# TrafficLights.net
KiCad netlist of a schematic drawn in EAGLE
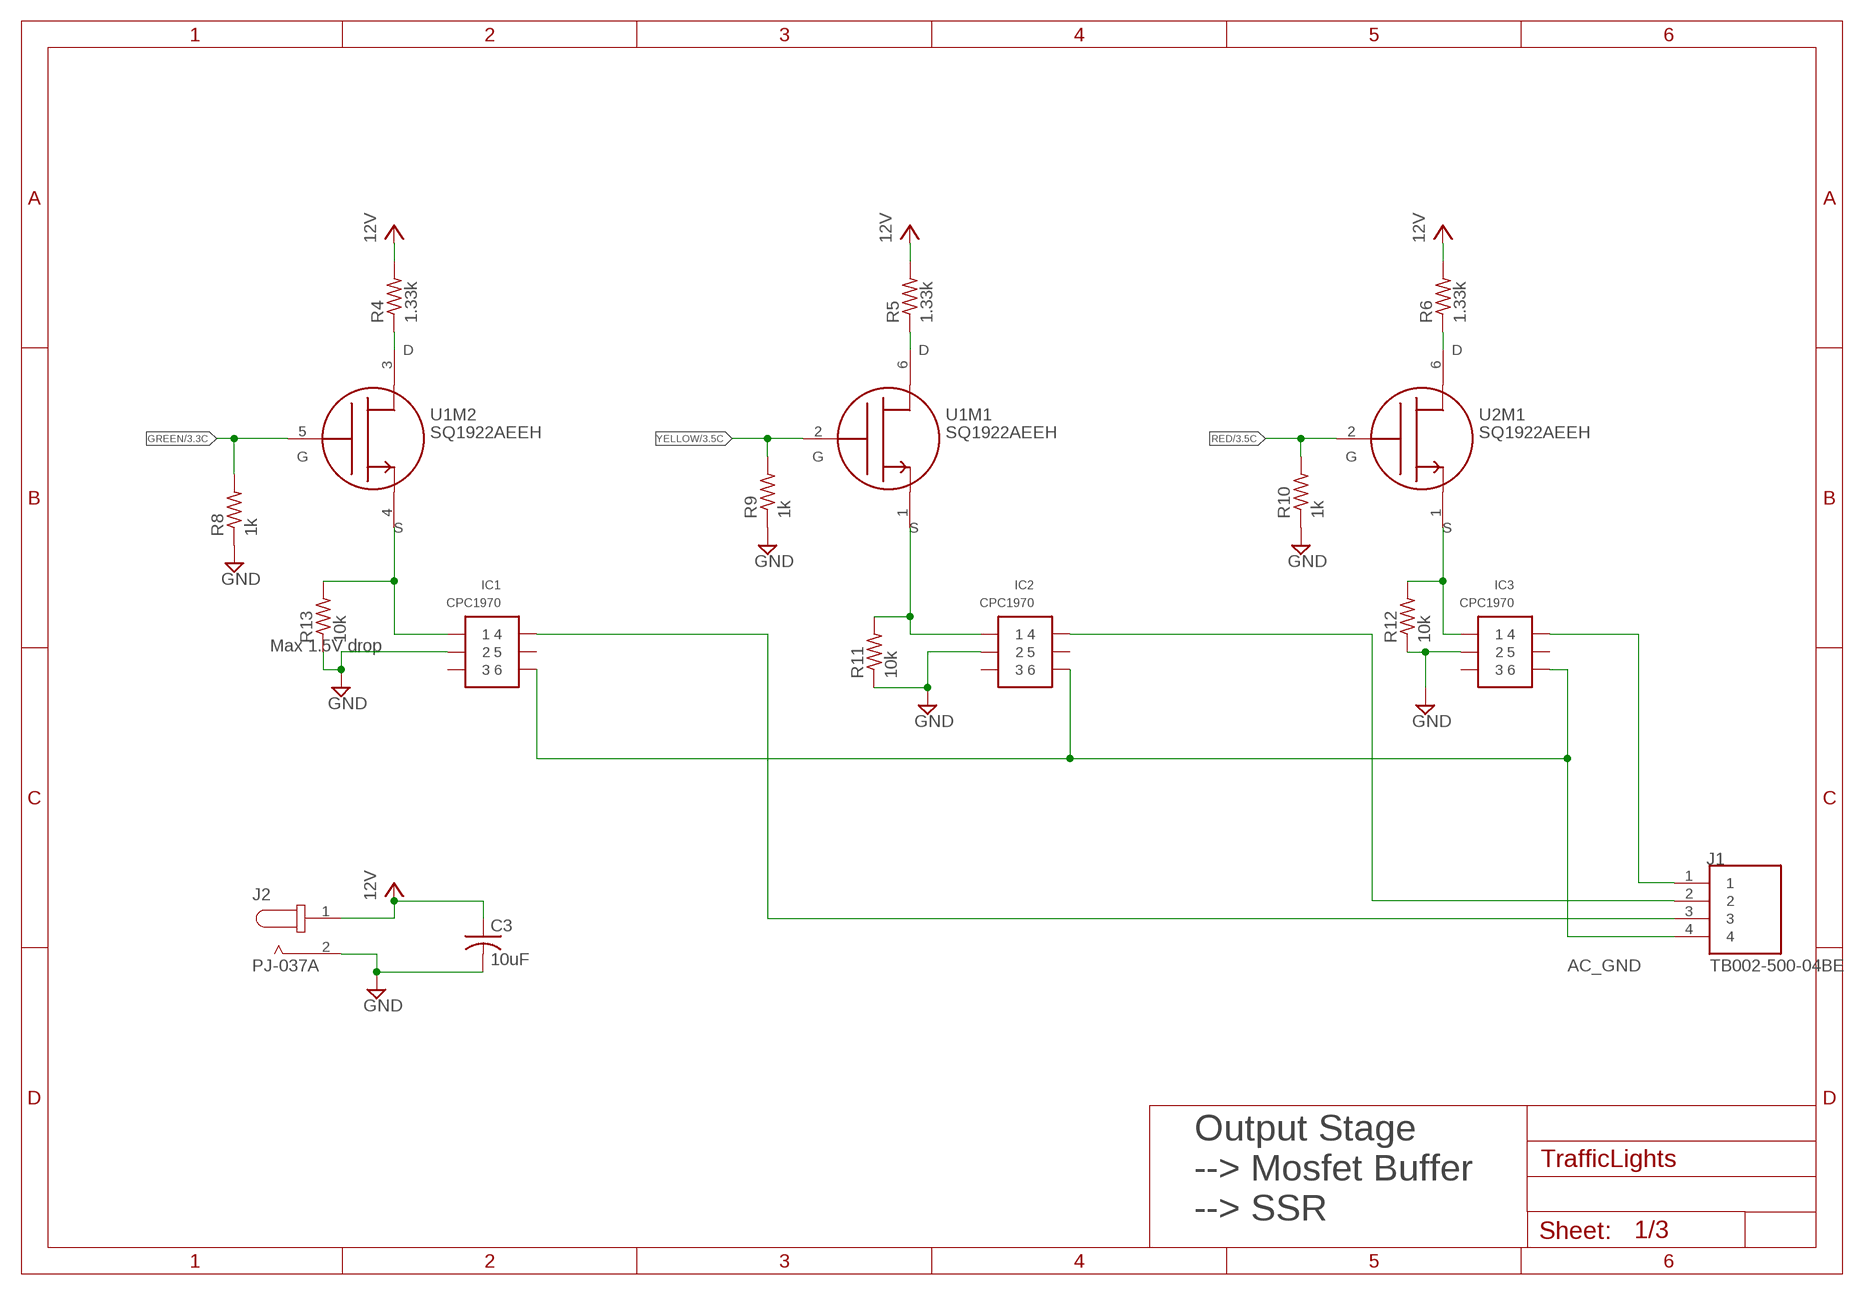
[diagram p0: schematic, sheet 1]
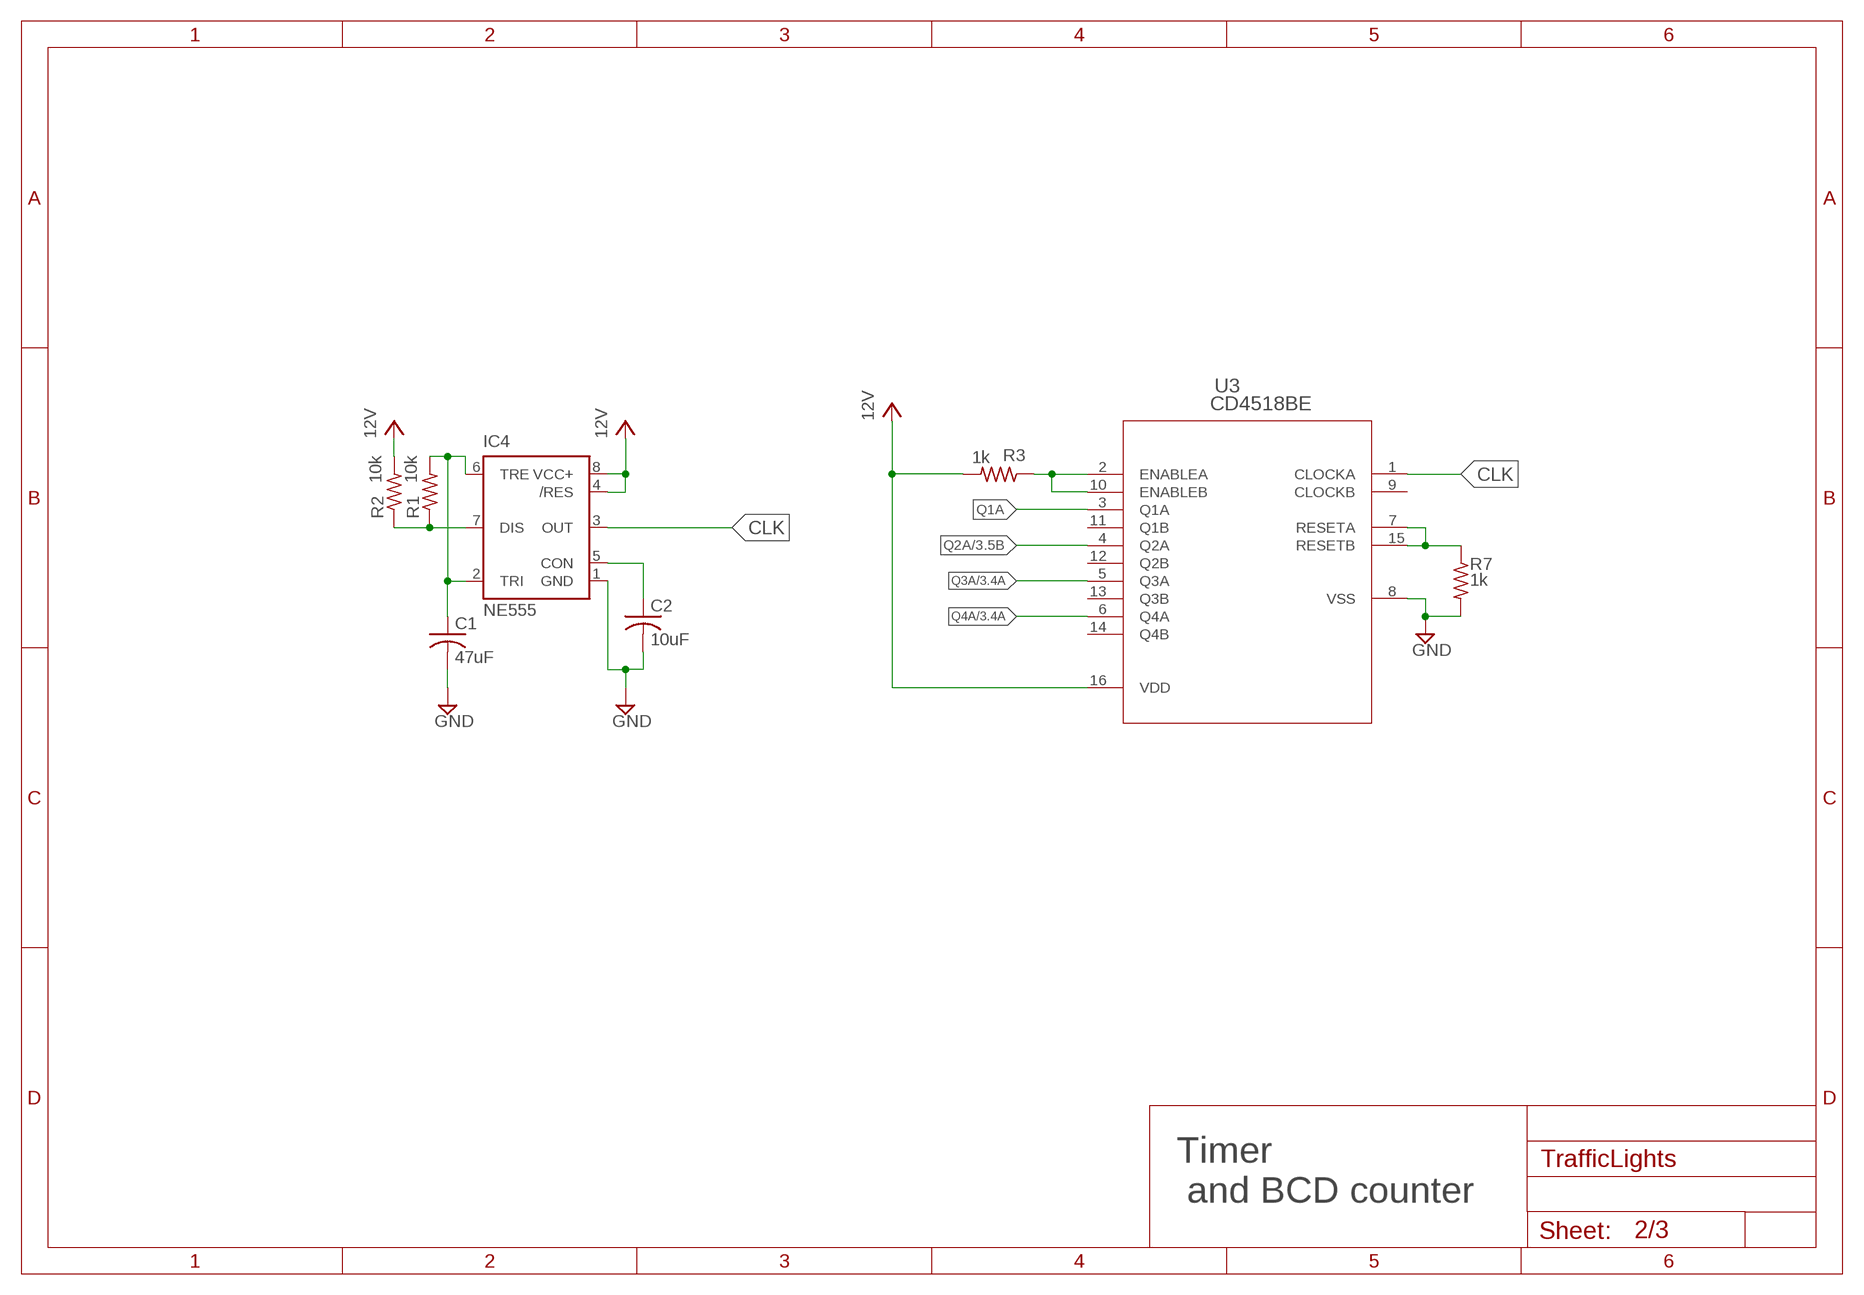
[diagram p1: schematic, sheet 2]
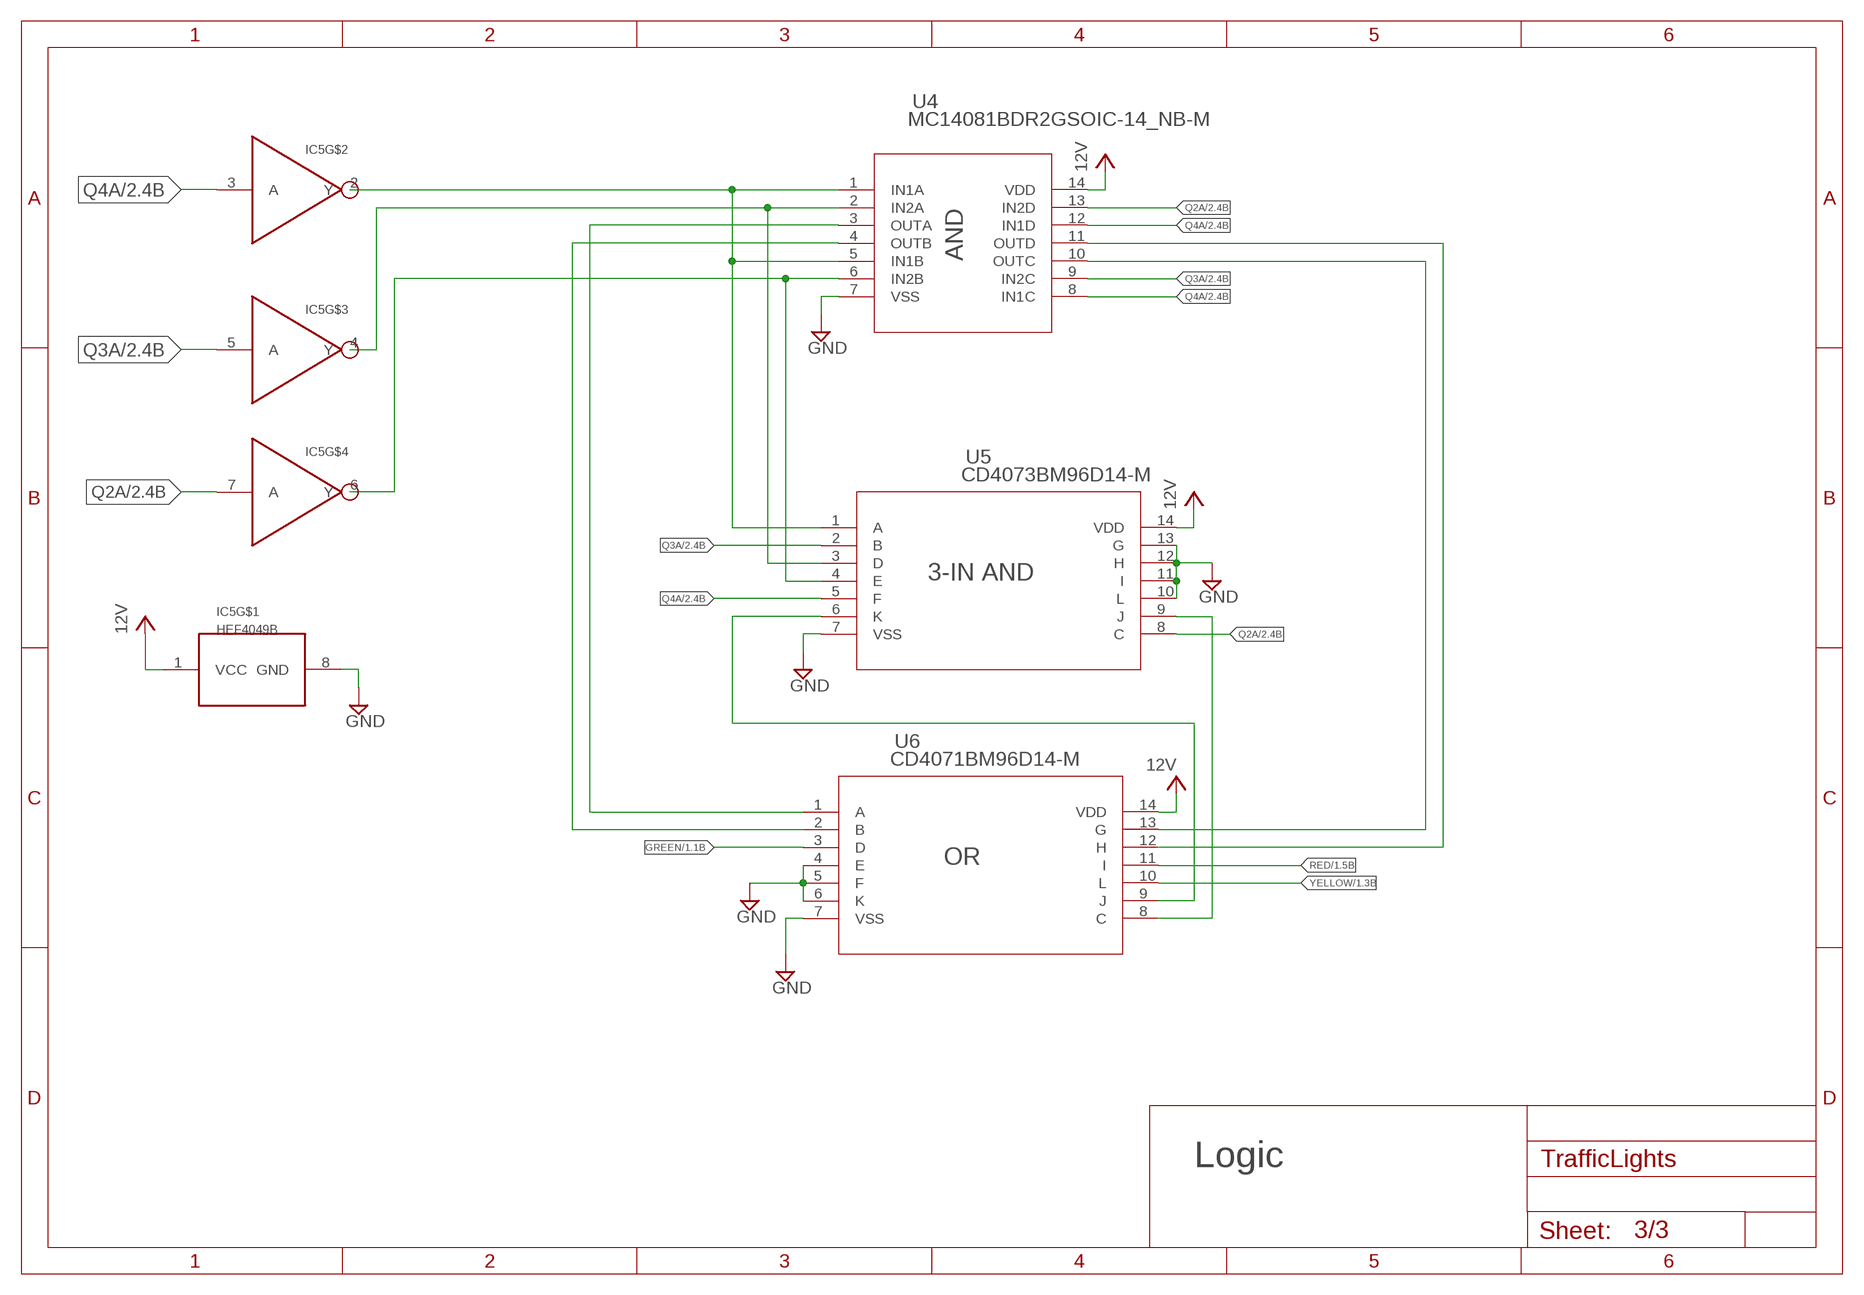
[diagram p2: schematic, sheet 3]

(export (version "E")
  (design (tool "Eeschema 10.0.6"))
  (components
    (comp (ref "IC5")
      (value "HEF4049B")
      (footprint "eagle-import:SO16")
      (libsource (lib "eagle-import") (part "HEF4049B"))
    )
    (comp (ref "U4")
      (value "MC14081BDR2GSOIC-14_NB-M")
      (footprint "eagle-import:SOIC-14_NB-M")
      (fields (field (name "MANUFACTURER_PART_NUMBER") "MC14081BDR2G"))
      (libsource (lib "eagle-import") (part "MC14081BDR2GSOIC-14_NB-M"))
    )
    (comp (ref "U5")
      (value "CD4073BM96D14-M")
      (footprint "eagle-import:D14-M")
      (fields (field (name "MANUFACTURER_PART_NUMBER") "CD4073BM96"))
      (libsource (lib "eagle-import") (part "CD4073BM96D14-M"))
    )
    (comp (ref "U6")
      (value "CD4071BM96D14-M")
      (footprint "eagle-import:D14-M")
      (fields (field (name "MANUFACTURER_PART_NUMBER") "CD4073BM96"))
      (libsource (lib "eagle-import") (part "CD4073BM96D14-M"))
    )
    (comp (ref "C1")
      (value "47uF")
      (footprint "eagle-import:C1206")
      (libsource (lib "eagle-import") (part "C-USC1206"))
    )
    (comp (ref "C2")
      (value "10uF")
      (footprint "eagle-import:C1206")
      (libsource (lib "eagle-import") (part "C-USC1206"))
    )
    (comp (ref "IC4")
      (value "NE555")
      (footprint "eagle-import:DIL-08")
      (fields (field (name "MF") "Arrow Electronics") (field (name "MPN") "NE555N"))
      (libsource (lib "eagle-import") (part "NE555"))
    )
    (comp (ref "R1")
      (value "10k")
      (footprint "eagle-import:R1206")
      (libsource (lib "eagle-import") (part "R-US_R1206"))
    )
    (comp (ref "R2")
      (value "10k")
      (footprint "eagle-import:R1206")
      (libsource (lib "eagle-import") (part "R-US_R1206"))
    )
    (comp (ref "R3")
      (value "1k")
      (footprint "eagle-import:R1206")
      (libsource (lib "eagle-import") (part "R-US_R1206"))
    )
    (comp (ref "R7")
      (value "1k")
      (footprint "eagle-import:R1206")
      (libsource (lib "eagle-import") (part "R-US_R1206"))
    )
    (comp (ref "U3")
      (value "CD4518BE")
      (footprint "eagle-import:N16")
      (libsource (lib "eagle-import") (part "CD4518BE"))
    )
    (comp (ref "C3")
      (value "10uF")
      (footprint "eagle-import:C1206")
      (libsource (lib "eagle-import") (part "C-USC1206"))
    )
    (comp (ref "IC1")
      (value "CPC1970")
      (footprint "eagle-import:6-DIP")
      (fields (field (name "MANUFACTURER_PART_NUMBER") "CPC1972G"))
      (libsource (lib "eagle-import") (part "CPC1972"))
    )
    (comp (ref "IC2")
      (value "CPC1970")
      (footprint "eagle-import:6-DIP")
      (fields (field (name "MANUFACTURER_PART_NUMBER") "CPC1972G"))
      (libsource (lib "eagle-import") (part "CPC1972"))
    )
    (comp (ref "IC3")
      (value "CPC1970")
      (footprint "eagle-import:6-DIP")
      (fields (field (name "MANUFACTURER_PART_NUMBER") "CPC1972G"))
      (libsource (lib "eagle-import") (part "CPC1972"))
    )
    (comp (ref "J1")
      (value "TB002-500-04BE")
      (footprint "eagle-import:CUI_TB002-500-04BE")
      (fields (field (name "MANUFACTURER") "CUI"))
      (libsource (lib "eagle-import") (part "TB002-500-04BE"))
    )
    (comp (ref "J2")
      (value "PJ-037A")
      (footprint "eagle-import:CUI_PJ-037A")
      (fields (field (name "DIGI-KEY_PART_NUMBER") "CP-037A-ND") (field (name "MF") "CUI Inc."))
      (libsource (lib "eagle-import") (part "PJ-037A"))
    )
    (comp (ref "R4")
      (value "1.33k")
      (footprint "eagle-import:R1206")
      (libsource (lib "eagle-import") (part "R-US_R1206"))
    )
    (comp (ref "R5")
      (value "1.33k")
      (footprint "eagle-import:R1206")
      (libsource (lib "eagle-import") (part "R-US_R1206"))
    )
    (comp (ref "R6")
      (value "1.33k")
      (footprint "eagle-import:R1206")
      (libsource (lib "eagle-import") (part "R-US_R1206"))
    )
    (comp (ref "R8")
      (value "1k")
      (footprint "eagle-import:R1206")
      (libsource (lib "eagle-import") (part "R-US_R1206"))
    )
    (comp (ref "R9")
      (value "1k")
      (footprint "eagle-import:R1206")
      (libsource (lib "eagle-import") (part "R-US_R1206"))
    )
    (comp (ref "R10")
      (value "1k")
      (footprint "eagle-import:R1206")
      (libsource (lib "eagle-import") (part "R-US_R1206"))
    )
    (comp (ref "R11")
      (value "10k")
      (footprint "eagle-import:0207_2V")
      (libsource (lib "eagle-import") (part "R-US_0207/2V"))
    )
    (comp (ref "R12")
      (value "10k")
      (footprint "eagle-import:0207_2V")
      (libsource (lib "eagle-import") (part "R-US_0207/2V"))
    )
    (comp (ref "R13")
      (value "10k")
      (footprint "eagle-import:R1206")
      (libsource (lib "eagle-import") (part "R-US_R1206"))
    )
    (comp (ref "U1")
      (value "SQ1922AEEH")
      (footprint "eagle-import:SOT-363")
      (fields (field (name "MANUFACTURER_PART_NUMBER") "SQ1922AEEH-T1_GE3"))
      (libsource (lib "eagle-import") (part "SQ1922AEEH"))
    )
    (comp (ref "U2")
      (value "SQ1922AEEH")
      (footprint "eagle-import:SOT-363")
      (fields (field (name "MANUFACTURER_PART_NUMBER") "SQ1922AEEH-T1_GE3"))
      (libsource (lib "eagle-import") (part "SQ1922AEEH"))
    )
  )
  (nets
    (net (code "1") (name "AC_GND") (class "Default")
      (node (ref "IC1") (pin "P$6") (pinfunction "6_P$6") (pintype "bidirectional"))
      (node (ref "IC2") (pin "P$6") (pinfunction "6_P$6") (pintype "bidirectional"))
      (node (ref "IC3") (pin "P$6") (pinfunction "6_P$6") (pintype "bidirectional"))
      (node (ref "J1") (pin "4") (pinfunction "4_4") (pintype "passive"))
    )
    (net (code "2") (name "CLK") (class "Default")
      (node (ref "IC4") (pin "3") (pinfunction "OUT_3") (pintype "output"))
      (node (ref "U3") (pin "1") (pinfunction "CLOCKA_1") (pintype "passive"))
    )
    (net (code "3") (name "GND") (class "Default")
      (node (ref "C1") (pin "2") (pinfunction "2_2") (pintype "passive"))
      (node (ref "C2") (pin "2") (pinfunction "2_2") (pintype "passive"))
      (node (ref "C3") (pin "2") (pinfunction "2_2") (pintype "passive"))
      (node (ref "IC1") (pin "P$2") (pinfunction "2_P$2") (pintype "bidirectional"))
      (node (ref "IC2") (pin "P$2") (pinfunction "2_P$2") (pintype "bidirectional"))
      (node (ref "IC3") (pin "P$2") (pinfunction "2_P$2") (pintype "bidirectional"))
      (node (ref "IC4") (pin "1") (pinfunction "GND_1") (pintype "power_in"))
      (node (ref "IC5") (pin "8") (pinfunction "GND_8") (pintype "bidirectional"))
      (node (ref "J2") (pin "2") (pinfunction "2_2") (pintype "passive"))
      (node (ref "R10") (pin "1") (pinfunction "1_1") (pintype "passive"))
      (node (ref "R11") (pin "1") (pinfunction "1_1") (pintype "passive"))
      (node (ref "R12") (pin "1") (pinfunction "1_1") (pintype "passive"))
      (node (ref "R13") (pin "1") (pinfunction "1_1") (pintype "passive"))
      (node (ref "R7") (pin "2") (pinfunction "2_2") (pintype "passive"))
      (node (ref "R8") (pin "1") (pinfunction "1_1") (pintype "passive"))
      (node (ref "R9") (pin "1") (pinfunction "1_1") (pintype "passive"))
      (node (ref "U3") (pin "8") (pinfunction "VSS_8") (pintype "power_in"))
      (node (ref "U4") (pin "7") (pinfunction "VSS_7") (pintype "power_in"))
      (node (ref "U5") (pin "10") (pinfunction "L_10") (pintype "passive"))
      (node (ref "U5") (pin "11") (pinfunction "I_11") (pintype "passive"))
      (node (ref "U5") (pin "12") (pinfunction "H_12") (pintype "passive"))
      (node (ref "U5") (pin "13") (pinfunction "G_13") (pintype "passive"))
      (node (ref "U5") (pin "7") (pinfunction "VSS_7") (pintype "power_in"))
      (node (ref "U6") (pin "4") (pinfunction "E_4") (pintype "passive"))
      (node (ref "U6") (pin "5") (pinfunction "F_5") (pintype "passive"))
      (node (ref "U6") (pin "6") (pinfunction "K_6") (pintype "passive"))
      (node (ref "U6") (pin "7") (pinfunction "VSS_7") (pintype "power_in"))
    )
    (net (code "4") (name "GREEN") (class "Default")
      (node (ref "R8") (pin "2") (pinfunction "2_2") (pintype "passive"))
      (node (ref "U1") (pin "5") (pinfunction "G_5") (pintype "bidirectional"))
      (node (ref "U6") (pin "3") (pinfunction "D_3") (pintype "passive"))
    )
    (net (code "5") (name "Net-(IC1-1)") (class "Default")
      (node (ref "IC1") (pin "P$1") (pinfunction "1_P$1") (pintype "bidirectional"))
      (node (ref "R13") (pin "2") (pinfunction "2_2") (pintype "passive"))
      (node (ref "U1") (pin "4") (pinfunction "S_4") (pintype "bidirectional"))
    )
    (net (code "6") (name "Net-(IC1-4)") (class "Default")
      (node (ref "IC1") (pin "P$4") (pinfunction "4_P$4") (pintype "bidirectional"))
      (node (ref "J1") (pin "3") (pinfunction "3_3") (pintype "passive"))
    )
    (net (code "7") (name "Net-(IC2-1)") (class "Default")
      (node (ref "IC2") (pin "P$1") (pinfunction "1_P$1") (pintype "bidirectional"))
      (node (ref "R11") (pin "2") (pinfunction "2_2") (pintype "passive"))
      (node (ref "U1") (pin "1") (pinfunction "S_1") (pintype "bidirectional"))
    )
    (net (code "8") (name "Net-(IC2-4)") (class "Default")
      (node (ref "IC2") (pin "P$4") (pinfunction "4_P$4") (pintype "bidirectional"))
      (node (ref "J1") (pin "2") (pinfunction "2_2") (pintype "passive"))
    )
    (net (code "9") (name "Net-(IC3-1)") (class "Default")
      (node (ref "IC3") (pin "P$1") (pinfunction "1_P$1") (pintype "bidirectional"))
      (node (ref "R12") (pin "2") (pinfunction "2_2") (pintype "passive"))
      (node (ref "U2") (pin "1") (pinfunction "S_1") (pintype "bidirectional"))
    )
    (net (code "10") (name "Net-(IC3-4)") (class "Default")
      (node (ref "IC3") (pin "P$4") (pinfunction "4_P$4") (pintype "bidirectional"))
      (node (ref "J1") (pin "1") (pinfunction "1_1") (pintype "passive"))
    )
    (net (code "11") (name "Net-(IC4-CON)") (class "Default")
      (node (ref "C2") (pin "1") (pinfunction "1_1") (pintype "passive"))
      (node (ref "IC4") (pin "5") (pinfunction "CON_5") (pintype "input"))
    )
    (net (code "12") (name "Net-(IC4-DIS)") (class "Default")
      (node (ref "IC4") (pin "7") (pinfunction "DIS_7") (pintype "input"))
      (node (ref "R1") (pin "1") (pinfunction "1_1") (pintype "passive"))
      (node (ref "R2") (pin "1") (pinfunction "1_1") (pintype "passive"))
    )
    (net (code "13") (name "Net-(IC4-TRE)") (class "Default")
      (node (ref "C1") (pin "1") (pinfunction "1_1") (pintype "passive"))
      (node (ref "IC4") (pin "2") (pinfunction "TRI_2") (pintype "input"))
      (node (ref "IC4") (pin "6") (pinfunction "TRE_6") (pintype "input"))
      (node (ref "R1") (pin "2") (pinfunction "2_2") (pintype "passive"))
    )
    (net (code "14") (name "Net-(IC5B-Y)") (class "Default")
      (node (ref "IC5") (pin "2") (pinfunction "Y_2") (pintype "bidirectional"))
      (node (ref "U4") (pin "1") (pinfunction "IN1A_1") (pintype "input"))
      (node (ref "U4") (pin "5") (pinfunction "IN1B_5") (pintype "input"))
      (node (ref "U5") (pin "1") (pinfunction "A_1") (pintype "passive"))
    )
    (net (code "15") (name "Net-(IC5C-Y)") (class "Default")
      (node (ref "IC5") (pin "4") (pinfunction "Y_4") (pintype "bidirectional"))
      (node (ref "U4") (pin "2") (pinfunction "IN2A_2") (pintype "input"))
      (node (ref "U5") (pin "3") (pinfunction "D_3") (pintype "passive"))
    )
    (net (code "16") (name "Net-(IC5D-Y)") (class "Default")
      (node (ref "IC5") (pin "6") (pinfunction "Y_6") (pintype "bidirectional"))
      (node (ref "U4") (pin "6") (pinfunction "IN2B_6") (pintype "input"))
      (node (ref "U5") (pin "4") (pinfunction "E_4") (pintype "passive"))
    )
    (net (code "17") (name "Net-(U1A-D)") (class "Default")
      (node (ref "R5") (pin "1") (pinfunction "1_1") (pintype "passive"))
      (node (ref "U1") (pin "6") (pinfunction "D_6") (pintype "bidirectional"))
    )
    (net (code "18") (name "Net-(U1B-D)") (class "Default")
      (node (ref "R4") (pin "1") (pinfunction "1_1") (pintype "passive"))
      (node (ref "U1") (pin "3") (pinfunction "D_3") (pintype "bidirectional"))
    )
    (net (code "19") (name "Net-(U2A-D)") (class "Default")
      (node (ref "R6") (pin "1") (pinfunction "1_1") (pintype "passive"))
      (node (ref "U2") (pin "6") (pinfunction "D_6") (pintype "bidirectional"))
    )
    (net (code "20") (name "Net-(U3-ENABLEA)") (class "Default")
      (node (ref "R3") (pin "1") (pinfunction "1_1") (pintype "passive"))
      (node (ref "U3") (pin "10") (pinfunction "ENABLEB_10") (pintype "passive"))
      (node (ref "U3") (pin "2") (pinfunction "ENABLEA_2") (pintype "passive"))
    )
    (net (code "21") (name "Net-(U3-RESETA)") (class "Default")
      (node (ref "R7") (pin "1") (pinfunction "1_1") (pintype "passive"))
      (node (ref "U3") (pin "15") (pinfunction "RESETB_15") (pintype "passive"))
      (node (ref "U3") (pin "7") (pinfunction "RESETA_7") (pintype "passive"))
    )
    (net (code "22") (name "Net-(U4-OUTA)") (class "Default")
      (node (ref "U4") (pin "3") (pinfunction "OUTA_3") (pintype "output"))
      (node (ref "U6") (pin "1") (pinfunction "A_1") (pintype "passive"))
    )
    (net (code "23") (name "Net-(U4-OUTB)") (class "Default")
      (node (ref "U4") (pin "4") (pinfunction "OUTB_4") (pintype "output"))
      (node (ref "U6") (pin "2") (pinfunction "B_2") (pintype "passive"))
    )
    (net (code "24") (name "Net-(U4-OUTC)") (class "Default")
      (node (ref "U4") (pin "10") (pinfunction "OUTC_10") (pintype "output"))
      (node (ref "U6") (pin "13") (pinfunction "G_13") (pintype "passive"))
    )
    (net (code "25") (name "Net-(U4-OUTD)") (class "Default")
      (node (ref "U4") (pin "11") (pinfunction "OUTD_11") (pintype "output"))
      (node (ref "U6") (pin "12") (pinfunction "H_12") (pintype "passive"))
    )
    (net (code "26") (name "Net-(U5-J)") (class "Default")
      (node (ref "U5") (pin "9") (pinfunction "J_9") (pintype "passive"))
      (node (ref "U6") (pin "8") (pinfunction "C_8") (pintype "passive"))
    )
    (net (code "27") (name "Net-(U5-K)") (class "Default")
      (node (ref "U5") (pin "6") (pinfunction "K_6") (pintype "passive"))
      (node (ref "U6") (pin "9") (pinfunction "J_9") (pintype "passive"))
    )
    (net (code "28") (name "Q1A") (class "Default")
      (node (ref "U3") (pin "3") (pinfunction "Q1A_3") (pintype "passive"))
    )
    (net (code "29") (name "Q2A") (class "Default")
      (node (ref "IC5") (pin "7") (pinfunction "A_7") (pintype "bidirectional"))
      (node (ref "U3") (pin "4") (pinfunction "Q2A_4") (pintype "passive"))
      (node (ref "U4") (pin "13") (pinfunction "IN2D_13") (pintype "input"))
      (node (ref "U5") (pin "8") (pinfunction "C_8") (pintype "passive"))
    )
    (net (code "30") (name "Q3A") (class "Default")
      (node (ref "IC5") (pin "5") (pinfunction "A_5") (pintype "bidirectional"))
      (node (ref "U3") (pin "5") (pinfunction "Q3A_5") (pintype "passive"))
      (node (ref "U4") (pin "9") (pinfunction "IN2C_9") (pintype "input"))
      (node (ref "U5") (pin "2") (pinfunction "B_2") (pintype "passive"))
    )
    (net (code "31") (name "Q4A") (class "Default")
      (node (ref "IC5") (pin "3") (pinfunction "A_3") (pintype "bidirectional"))
      (node (ref "U3") (pin "6") (pinfunction "Q4A_6") (pintype "passive"))
      (node (ref "U4") (pin "12") (pinfunction "IN1D_12") (pintype "input"))
      (node (ref "U4") (pin "8") (pinfunction "IN1C_8") (pintype "input"))
      (node (ref "U5") (pin "5") (pinfunction "F_5") (pintype "passive"))
    )
    (net (code "32") (name "RED") (class "Default")
      (node (ref "R10") (pin "2") (pinfunction "2_2") (pintype "passive"))
      (node (ref "U2") (pin "2") (pinfunction "G_2") (pintype "bidirectional"))
      (node (ref "U6") (pin "11") (pinfunction "I_11") (pintype "passive"))
    )
    (net (code "33") (name "VCC") (class "Default")
      (node (ref "C3") (pin "1") (pinfunction "1_1") (pintype "passive"))
      (node (ref "IC4") (pin "4") (pinfunction "/RES_4") (pintype "input"))
      (node (ref "IC4") (pin "8") (pinfunction "VCC+_8") (pintype "power_in"))
      (node (ref "IC5") (pin "1") (pinfunction "VCC_1") (pintype "power_in"))
      (node (ref "J2") (pin "1") (pinfunction "1_1") (pintype "passive"))
      (node (ref "R2") (pin "2") (pinfunction "2_2") (pintype "passive"))
      (node (ref "R3") (pin "2") (pinfunction "2_2") (pintype "passive"))
      (node (ref "R4") (pin "2") (pinfunction "2_2") (pintype "passive"))
      (node (ref "R5") (pin "2") (pinfunction "2_2") (pintype "passive"))
      (node (ref "R6") (pin "2") (pinfunction "2_2") (pintype "passive"))
      (node (ref "U3") (pin "16") (pinfunction "VDD_16") (pintype "power_in"))
      (node (ref "U4") (pin "14") (pinfunction "VDD_14") (pintype "power_in"))
      (node (ref "U5") (pin "14") (pinfunction "VDD_14") (pintype "power_in"))
      (node (ref "U6") (pin "14") (pinfunction "VDD_14") (pintype "power_in"))
    )
    (net (code "34") (name "YELLOW") (class "Default")
      (node (ref "R9") (pin "2") (pinfunction "2_2") (pintype "passive"))
      (node (ref "U1") (pin "2") (pinfunction "G_2") (pintype "bidirectional"))
      (node (ref "U6") (pin "10") (pinfunction "L_10") (pintype "passive"))
    )
    (net (code "35") (name "unconnected-(IC1-3-PadP$3)") (class "Default")
      (node (ref "IC1") (pin "P$3") (pinfunction "3_P$3") (pintype "no_connect"))
    )
    (net (code "36") (name "unconnected-(IC1-5-PadP$5)") (class "Default")
      (node (ref "IC1") (pin "P$5") (pinfunction "5_P$5") (pintype "no_connect"))
    )
    (net (code "37") (name "unconnected-(IC2-3-PadP$3)") (class "Default")
      (node (ref "IC2") (pin "P$3") (pinfunction "3_P$3") (pintype "no_connect"))
    )
    (net (code "38") (name "unconnected-(IC2-5-PadP$5)") (class "Default")
      (node (ref "IC2") (pin "P$5") (pinfunction "5_P$5") (pintype "no_connect"))
    )
    (net (code "39") (name "unconnected-(IC3-3-PadP$3)") (class "Default")
      (node (ref "IC3") (pin "P$3") (pinfunction "3_P$3") (pintype "no_connect"))
    )
    (net (code "40") (name "unconnected-(IC3-5-PadP$5)") (class "Default")
      (node (ref "IC3") (pin "P$5") (pinfunction "5_P$5") (pintype "no_connect"))
    )
    (net (code "41") (name "unconnected-(U3-CLOCKB-Pad9)") (class "Default")
      (node (ref "U3") (pin "9") (pinfunction "CLOCKB_9") (pintype "passive"))
    )
    (net (code "42") (name "unconnected-(U3-Q1B-Pad11)") (class "Default")
      (node (ref "U3") (pin "11") (pinfunction "Q1B_11") (pintype "passive"))
    )
    (net (code "43") (name "unconnected-(U3-Q2B-Pad12)") (class "Default")
      (node (ref "U3") (pin "12") (pinfunction "Q2B_12") (pintype "passive"))
    )
    (net (code "44") (name "unconnected-(U3-Q3B-Pad13)") (class "Default")
      (node (ref "U3") (pin "13") (pinfunction "Q3B_13") (pintype "passive"))
    )
    (net (code "45") (name "unconnected-(U3-Q4B-Pad14)") (class "Default")
      (node (ref "U3") (pin "14") (pinfunction "Q4B_14") (pintype "passive"))
    )
  )
)
